# Parachute_V1.net
KiCad netlist of a schematic drawn in EAGLE
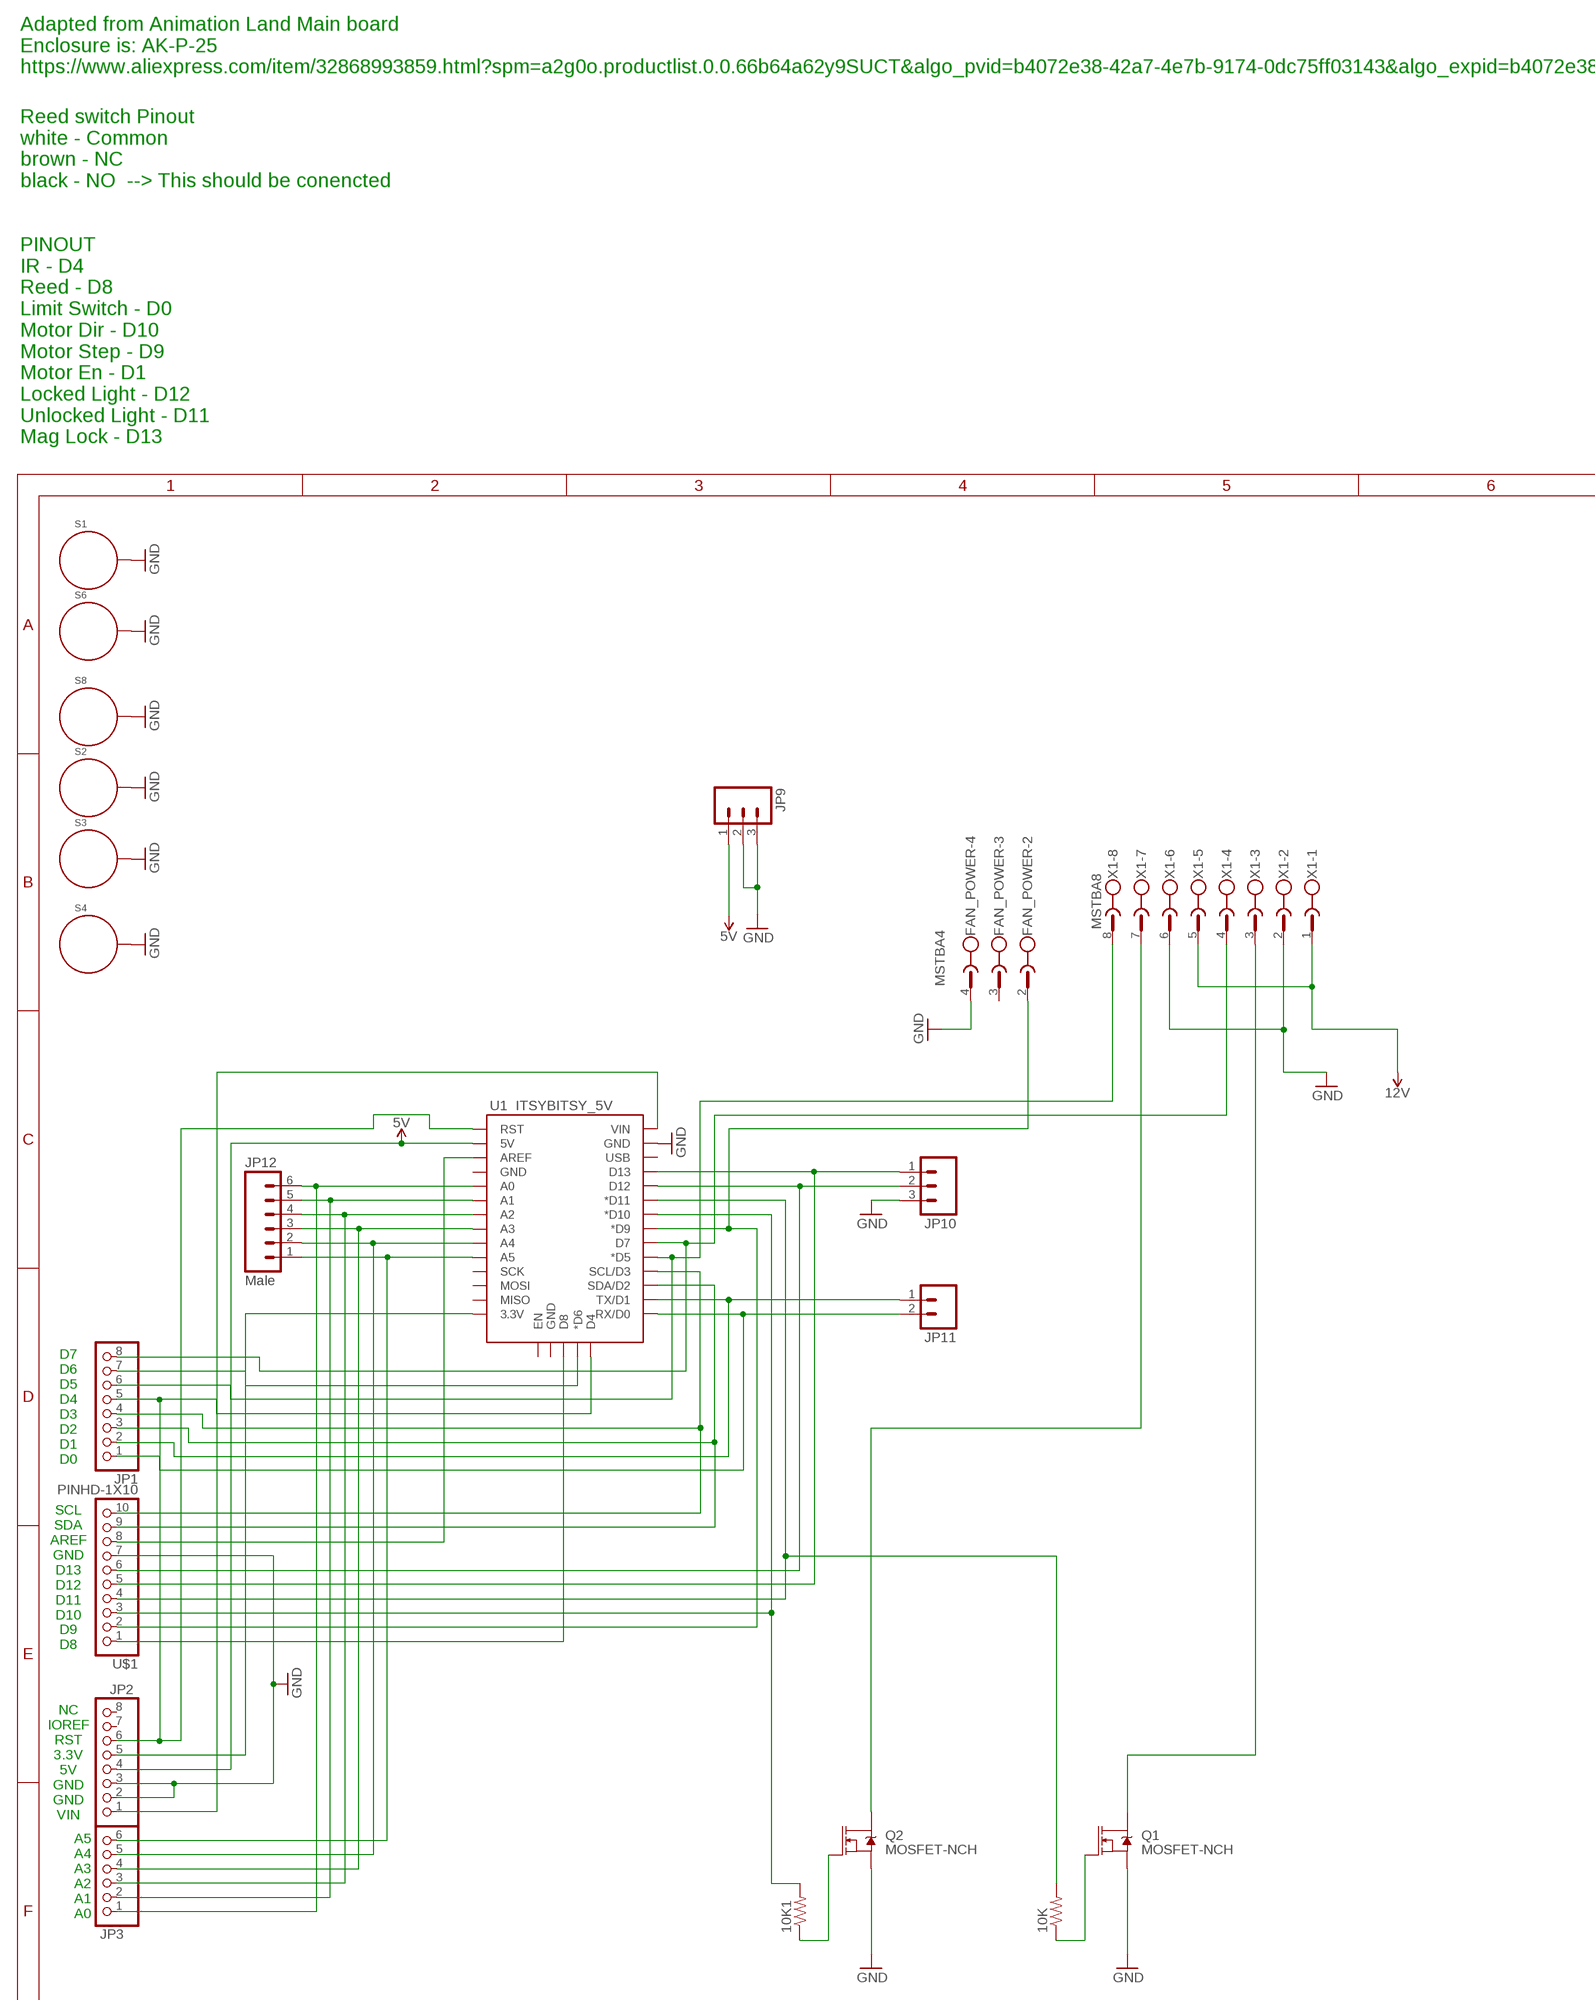
[diagram p0: schematic, sheet 1, part 1 of 2]
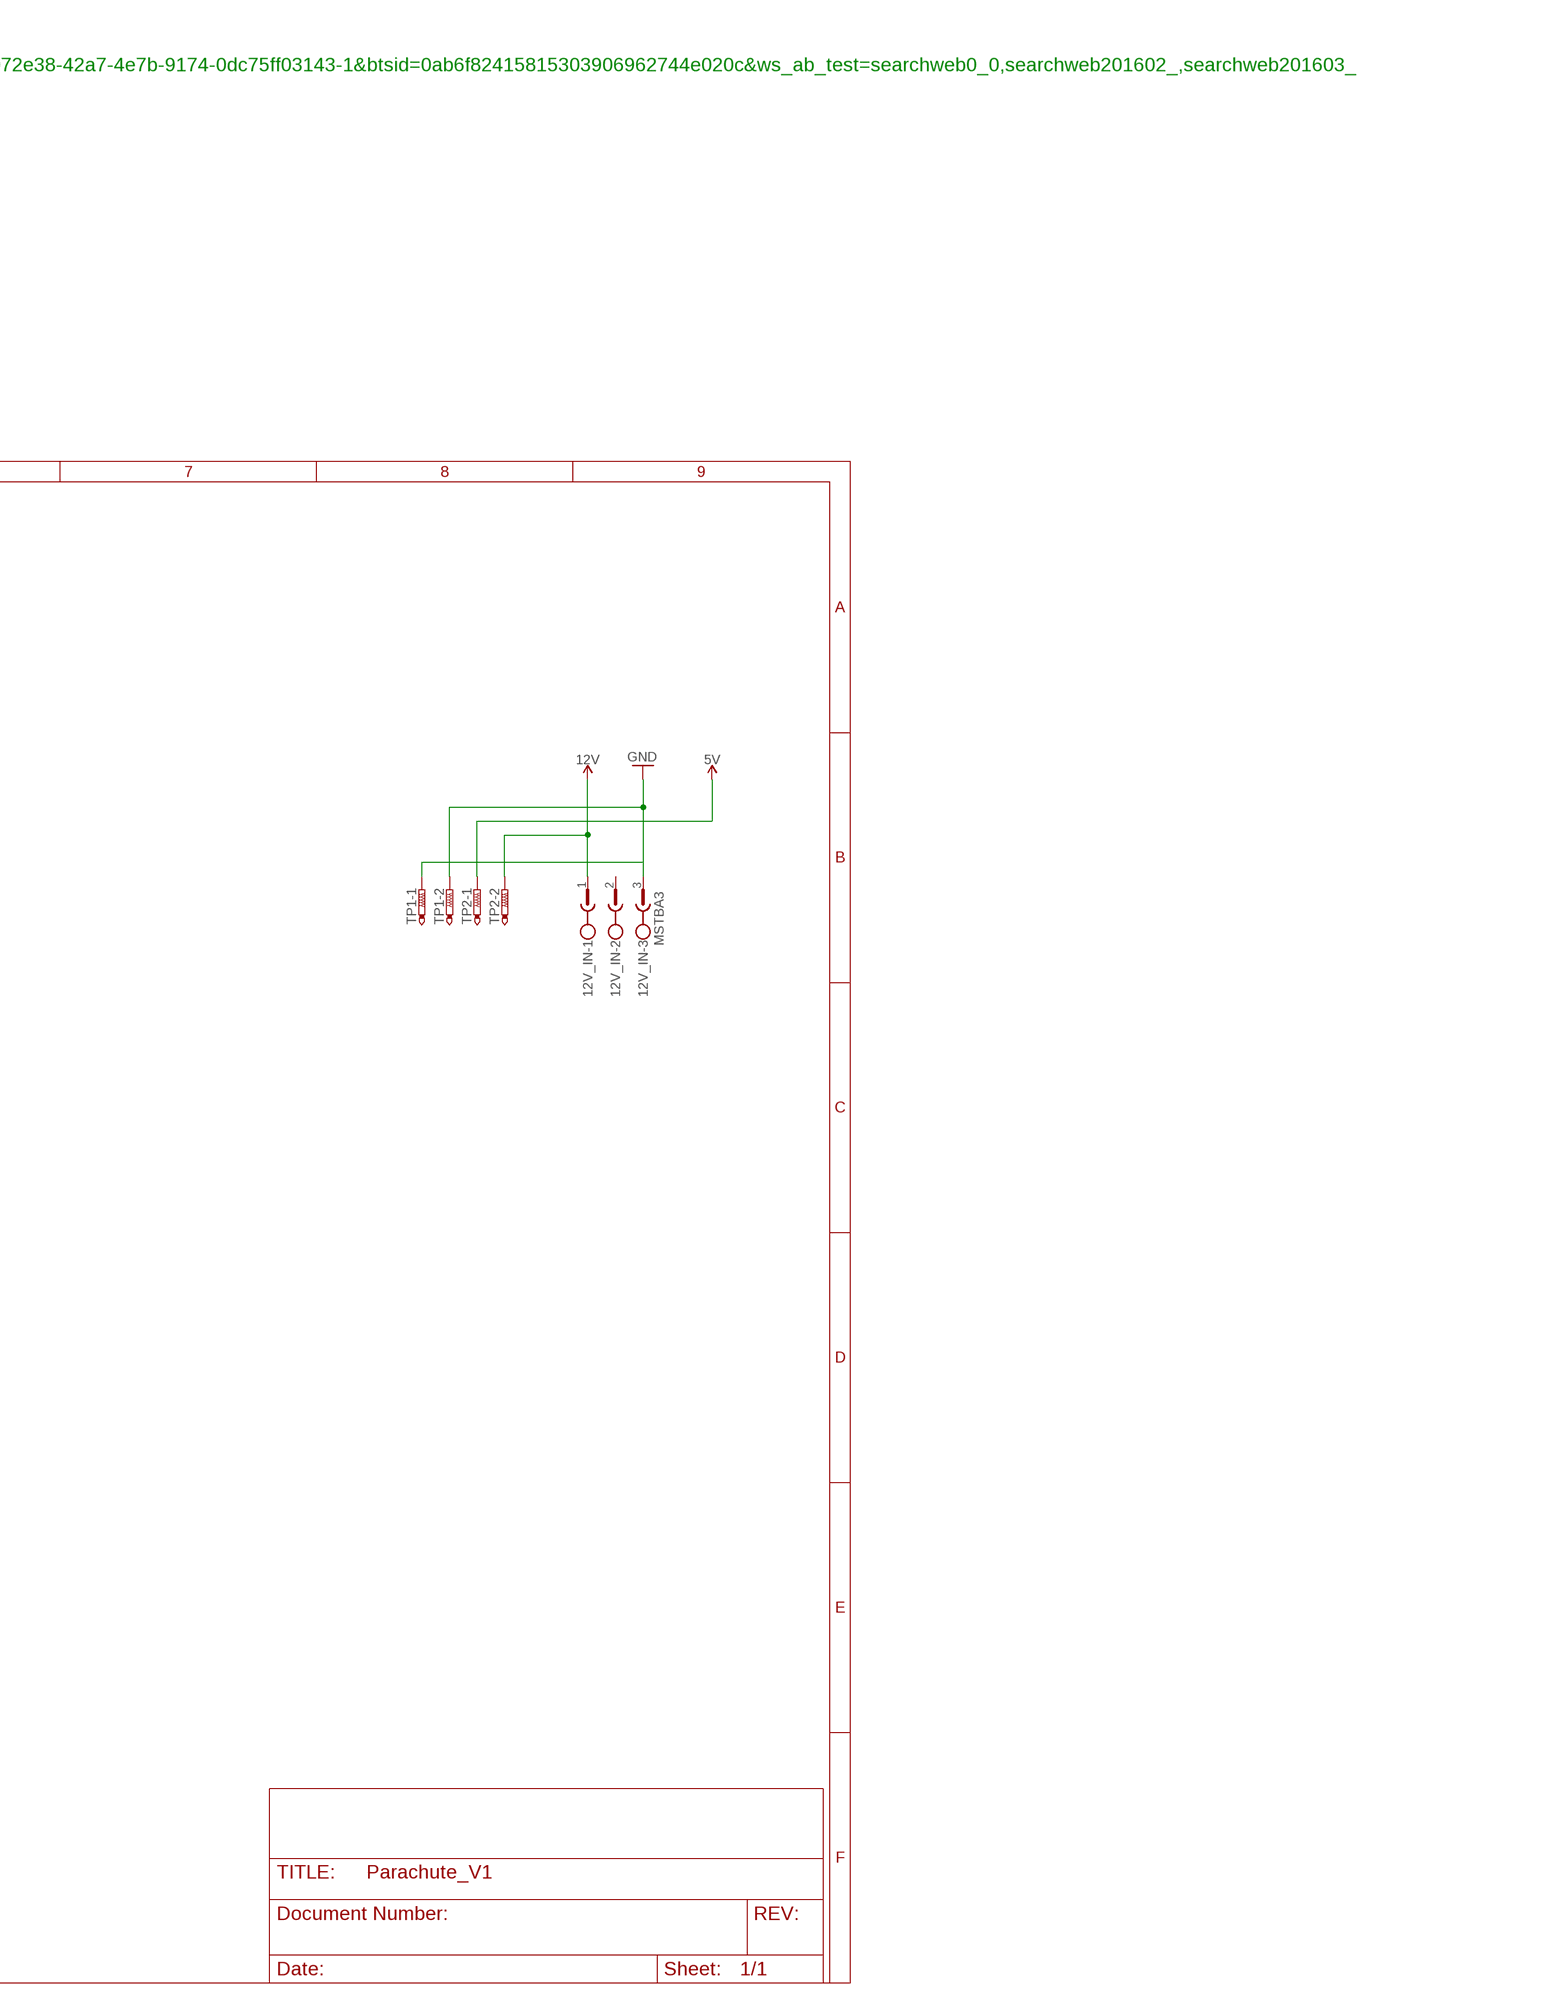
[diagram p1: schematic, sheet 1, part 2 of 2]

(export (version "E")
  (design (tool "Eeschema 10.0.6"))
  (components
    (comp (ref "10K")
      (value "R-US_M0805")
      (footprint "eagle-import:M0805")
      (libsource (lib "eagle-import") (part "R-US_M0805"))
    )
    (comp (ref "10K1")
      (value "R-US_M0805")
      (footprint "eagle-import:M0805")
      (libsource (lib "eagle-import") (part "R-US_M0805"))
    )
    (comp (ref "12V_IN")
      (value "MSTBA3")
      (footprint "eagle-import:MSTBA3")
      (fields (field (name "MF") "FARNELL") (field (name "MPN") "1757255"))
      (libsource (lib "eagle-import") (part "MSTBA3"))
    )
    (comp (ref "FAN_POWER")
      (value "MSTBA4")
      (footprint "eagle-import:MSTBA4")
      (fields (field (name "MF") "FARNELL") (field (name "MPN") "1757268"))
      (libsource (lib "eagle-import") (part "MSTBA4"))
    )
    (comp (ref "JP1")
      (value "PINHD-1X8CLEANBIG")
      (footprint "eagle-import:1X08-CLEANBIG")
      (libsource (lib "eagle-import") (part "PINHD-1X8CLEANBIG"))
    )
    (comp (ref "JP2")
      (value "PINHD-1X8CLEANBIG")
      (footprint "eagle-import:1X08-CLEANBIG")
      (libsource (lib "eagle-import") (part "PINHD-1X8CLEANBIG"))
    )
    (comp (ref "JP3")
      (value "PINHD-1X6B")
      (footprint "eagle-import:1X06-BIG")
      (libsource (lib "eagle-import") (part "PINHD-1X6B"))
    )
    (comp (ref "JP9")
      (value "M031X03_NO_SILK")
      (footprint "eagle-import:1X03_NO_SILK")
      (libsource (lib "eagle-import") (part "M031X03_NO_SILK"))
    )
    (comp (ref "JP10")
      (value "M031X03_NO_SILK")
      (footprint "eagle-import:1X03_NO_SILK")
      (libsource (lib "eagle-import") (part "M031X03_NO_SILK"))
    )
    (comp (ref "JP11")
      (value "M021X02_NO_SILK")
      (footprint "eagle-import:1X02_NO_SILK")
      (libsource (lib "eagle-import") (part "M021X02_NO_SILK"))
    )
    (comp (ref "JP12")
      (value "Male")
      (footprint "eagle-import:1X06")
      (libsource (lib "eagle-import") (part "M06SIP"))
    )
    (comp (ref "Q1")
      (value "MOSFET-NCH")
      (footprint "eagle-import:SO-8_POWER_PAK")
      (libsource (lib "eagle-import") (part "MOSFET-NCH"))
    )
    (comp (ref "Q2")
      (value "MOSFET-NCH")
      (footprint "eagle-import:SO-8_POWER_PAK")
      (libsource (lib "eagle-import") (part "MOSFET-NCH"))
    )
    (comp (ref "S1")
      (value "STANDOFF_ELECTRICAL5-32")
      (footprint "eagle-import:STANDOFF_ELECTRICAL_5_32")
      (libsource (lib "eagle-import") (part "STANDOFF_ELECTRICAL5-32"))
    )
    (comp (ref "S2")
      (value "STANDOFF_ELECTRICAL5-32")
      (footprint "eagle-import:STANDOFF_ELECTRICAL_5_32")
      (libsource (lib "eagle-import") (part "STANDOFF_ELECTRICAL5-32"))
    )
    (comp (ref "S3")
      (value "STANDOFF_ELECTRICAL5-32")
      (footprint "eagle-import:STANDOFF_ELECTRICAL_5_32")
      (libsource (lib "eagle-import") (part "STANDOFF_ELECTRICAL5-32"))
    )
    (comp (ref "S4")
      (value "STANDOFF_ELECTRICAL5-32")
      (footprint "eagle-import:STANDOFF_ELECTRICAL_5_32")
      (libsource (lib "eagle-import") (part "STANDOFF_ELECTRICAL5-32"))
    )
    (comp (ref "S6")
      (value "STANDOFF_ELECTRICAL5-32")
      (footprint "eagle-import:STANDOFF_ELECTRICAL_5_32")
      (libsource (lib "eagle-import") (part "STANDOFF_ELECTRICAL5-32"))
    )
    (comp (ref "S8")
      (value "STANDOFF_ELECTRICAL5-32")
      (footprint "eagle-import:STANDOFF_ELECTRICAL_5_32")
      (libsource (lib "eagle-import") (part "STANDOFF_ELECTRICAL5-32"))
    )
    (comp (ref "TP1")
      (value "PTR2")
      (footprint "eagle-import:P2-38-17")
      (libsource (lib "eagle-import") (part "PTR2"))
    )
    (comp (ref "TP2")
      (value "PTR2")
      (footprint "eagle-import:P2-38-17")
      (libsource (lib "eagle-import") (part "PTR2"))
    )
    (comp (ref "U$1")
      (value "PINHD-1X10")
      (footprint "eagle-import:1X10-BIG")
      (libsource (lib "eagle-import") (part "PINHD-1X10"))
    )
    (comp (ref "U1")
      (value "ITSYBITSY_5V")
      (footprint "eagle-import:ADAFRUIT_LENOARDO")
      (libsource (lib "eagle-import") (part "ITSYBITSY_5V"))
    )
    (comp (ref "X1")
      (value "MSTBA8")
      (footprint "eagle-import:MSTBA8")
      (fields (field (name "MF") "FARNELL") (field (name "MPN") "1757307"))
      (libsource (lib "eagle-import") (part "MSTBA8"))
    )
  )
  (nets
    (net (code "1") (name "5V") (class "Default")
      (node (ref "JP2") (pin "4") (pinfunction "4_4") (pintype "passive"))
      (node (ref "JP9") (pin "1") (pinfunction "1_1") (pintype "passive"))
      (node (ref "TP2") (pin "TP-1") (pinfunction "TP_TP-1") (pintype "input"))
      (node (ref "U1") (pin "5V") (pinfunction "5V_5V") (pintype "bidirectional"))
    )
    (net (code "2") (name "12V") (class "Default")
      (node (ref "12V_IN") (pin "1") (pinfunction "1_1") (pintype "passive"))
      (node (ref "TP2") (pin "TP-2") (pinfunction "TP_TP-2") (pintype "input"))
      (node (ref "X1") (pin "1") (pinfunction "1_1") (pintype "passive"))
      (node (ref "X1") (pin "5") (pinfunction "1_5") (pintype "passive"))
    )
    (net (code "3") (name "GND") (class "Default")
      (node (ref "12V_IN") (pin "3") (pinfunction "1_3") (pintype "passive"))
      (node (ref "FAN_POWER") (pin "4") (pinfunction "1_4") (pintype "passive"))
      (node (ref "JP10") (pin "3") (pinfunction "3_3") (pintype "passive"))
      (node (ref "JP2") (pin "2") (pinfunction "2_2") (pintype "passive"))
      (node (ref "JP2") (pin "3") (pinfunction "3_3") (pintype "passive"))
      (node (ref "JP9") (pin "2") (pinfunction "2_2") (pintype "passive"))
      (node (ref "JP9") (pin "3") (pinfunction "3_3") (pintype "passive"))
      (node (ref "Q1") (pin "S") (pinfunction "S_S") (pintype "bidirectional"))
      (node (ref "Q2") (pin "S") (pinfunction "S_S") (pintype "bidirectional"))
      (node (ref "S1") (pin "P1") (pinfunction "P$1_P1") (pintype "bidirectional"))
      (node (ref "S2") (pin "P1") (pinfunction "P$1_P1") (pintype "bidirectional"))
      (node (ref "S3") (pin "P1") (pinfunction "P$1_P1") (pintype "bidirectional"))
      (node (ref "S4") (pin "P1") (pinfunction "P$1_P1") (pintype "bidirectional"))
      (node (ref "S6") (pin "P1") (pinfunction "P$1_P1") (pintype "bidirectional"))
      (node (ref "S8") (pin "P1") (pinfunction "P$1_P1") (pintype "bidirectional"))
      (node (ref "TP1") (pin "TP-1") (pinfunction "TP_TP-1") (pintype "input"))
      (node (ref "TP1") (pin "TP-2") (pinfunction "TP_TP-2") (pintype "input"))
      (node (ref "U$1") (pin "7") (pinfunction "7_7") (pintype "passive"))
      (node (ref "U1") (pin "GND@2") (pinfunction "GND_GND@2") (pintype "bidirectional"))
      (node (ref "X1") (pin "2") (pinfunction "1_2") (pintype "passive"))
      (node (ref "X1") (pin "6") (pinfunction "1_6") (pintype "passive"))
    )
    (net (code "4") (name "Net-(10K-Pad1)") (class "Default")
      (node (ref "10K") (pin "1") (pinfunction "1_1") (pintype "passive"))
      (node (ref "Q1") (pin "G") (pinfunction "G_G") (pintype "bidirectional"))
    )
    (net (code "5") (name "Net-(10K1-Pad1)") (class "Default")
      (node (ref "10K1") (pin "1") (pinfunction "1_1") (pintype "passive"))
      (node (ref "Q2") (pin "G") (pinfunction "G_G") (pintype "bidirectional"))
    )
    (net (code "6") (name "Net-(FAN_POWERB-1)") (class "Default")
      (node (ref "FAN_POWER") (pin "2") (pinfunction "1_2") (pintype "passive"))
      (node (ref "U$1") (pin "2") (pinfunction "2_2") (pintype "passive"))
      (node (ref "U1") (pin "D9") (pinfunction "*D9_D9") (pintype "bidirectional"))
    )
    (net (code "7") (name "Net-(JP2-Pad1)") (class "Default")
      (node (ref "JP2") (pin "1") (pinfunction "1_1") (pintype "passive"))
      (node (ref "U1") (pin "VIN") (pinfunction "VIN_VIN") (pintype "bidirectional"))
    )
    (net (code "8") (name "Net-(JP10-Pad1)") (class "Default")
      (node (ref "JP10") (pin "1") (pinfunction "1_1") (pintype "passive"))
      (node (ref "U$1") (pin "5") (pinfunction "5_5") (pintype "passive"))
      (node (ref "U1") (pin "D13") (pinfunction "D13_D13") (pintype "bidirectional"))
    )
    (net (code "9") (name "Net-(JP10-Pad2)") (class "Default")
      (node (ref "JP10") (pin "2") (pinfunction "2_2") (pintype "passive"))
      (node (ref "U$1") (pin "6") (pinfunction "6_6") (pintype "passive"))
      (node (ref "U1") (pin "D12") (pinfunction "D12_D12") (pintype "bidirectional"))
    )
    (net (code "10") (name "Net-(JP12-Pad1)") (class "Default")
      (node (ref "JP12") (pin "1") (pinfunction "1_1") (pintype "passive"))
      (node (ref "JP3") (pin "6") (pinfunction "6_6") (pintype "passive"))
      (node (ref "U1") (pin "A5") (pinfunction "A5_A5") (pintype "bidirectional"))
    )
    (net (code "11") (name "Net-(JP12-Pad2)") (class "Default")
      (node (ref "JP12") (pin "2") (pinfunction "2_2") (pintype "passive"))
      (node (ref "JP3") (pin "5") (pinfunction "5_5") (pintype "passive"))
      (node (ref "U1") (pin "A4") (pinfunction "A4_A4") (pintype "bidirectional"))
    )
    (net (code "12") (name "Net-(JP12-Pad3)") (class "Default")
      (node (ref "JP12") (pin "3") (pinfunction "3_3") (pintype "passive"))
      (node (ref "JP3") (pin "4") (pinfunction "4_4") (pintype "passive"))
      (node (ref "U1") (pin "A3") (pinfunction "A3_A3") (pintype "bidirectional"))
    )
    (net (code "13") (name "Net-(JP12-Pad4)") (class "Default")
      (node (ref "JP12") (pin "4") (pinfunction "4_4") (pintype "passive"))
      (node (ref "JP3") (pin "3") (pinfunction "3_3") (pintype "passive"))
      (node (ref "U1") (pin "A2") (pinfunction "A2_A2") (pintype "bidirectional"))
    )
    (net (code "14") (name "Net-(JP12-Pad5)") (class "Default")
      (node (ref "JP12") (pin "5") (pinfunction "5_5") (pintype "passive"))
      (node (ref "JP3") (pin "2") (pinfunction "2_2") (pintype "passive"))
      (node (ref "U1") (pin "A1") (pinfunction "A1_A1") (pintype "bidirectional"))
    )
    (net (code "15") (name "Net-(JP12-Pad6)") (class "Default")
      (node (ref "JP12") (pin "6") (pinfunction "6_6") (pintype "passive"))
      (node (ref "JP3") (pin "1") (pinfunction "1_1") (pintype "passive"))
      (node (ref "U1") (pin "A0") (pinfunction "A0_A0") (pintype "bidirectional"))
    )
    (net (code "16") (name "Net-(Q1-D)") (class "Default")
      (node (ref "Q1") (pin "D1") (pinfunction "D_D1") (pintype "bidirectional"))
      (node (ref "X1") (pin "3") (pinfunction "1_3") (pintype "passive"))
    )
    (net (code "17") (name "Net-(Q2-D)") (class "Default")
      (node (ref "Q2") (pin "D1") (pinfunction "D_D1") (pintype "bidirectional"))
      (node (ref "X1") (pin "7") (pinfunction "1_7") (pintype "passive"))
    )
    (net (code "18") (name "Net-(U$1-Pad1)") (class "Default")
      (node (ref "U$1") (pin "1") (pinfunction "1_1") (pintype "passive"))
      (node (ref "U1") (pin "D8") (pinfunction "D8_D8") (pintype "bidirectional"))
    )
    (net (code "19") (name "Net-(U$1-Pad8)") (class "Default")
      (node (ref "U$1") (pin "8") (pinfunction "8_8") (pintype "passive"))
      (node (ref "U1") (pin "AREF") (pinfunction "AREF_AREF") (pintype "bidirectional"))
    )
    (net (code "20") (name "Net-(U1-*D5)") (class "Default")
      (node (ref "JP1") (pin "6") (pinfunction "6_6") (pintype "passive"))
      (node (ref "U1") (pin "D5") (pinfunction "*D5_D5") (pintype "bidirectional"))
      (node (ref "X1") (pin "8") (pinfunction "1_8") (pintype "passive"))
    )
    (net (code "21") (name "Net-(U1-*D6)") (class "Default")
      (node (ref "JP1") (pin "7") (pinfunction "7_7") (pintype "passive"))
      (node (ref "U1") (pin "D6") (pinfunction "*D6_D6") (pintype "bidirectional"))
    )
    (net (code "22") (name "Net-(U1-*D10)") (class "Default")
      (node (ref "10K1") (pin "2") (pinfunction "2_2") (pintype "passive"))
      (node (ref "U$1") (pin "3") (pinfunction "3_3") (pintype "passive"))
      (node (ref "U1") (pin "D10") (pinfunction "*D10_D10") (pintype "bidirectional"))
    )
    (net (code "23") (name "Net-(U1-*D11)") (class "Default")
      (node (ref "10K") (pin "2") (pinfunction "2_2") (pintype "passive"))
      (node (ref "U$1") (pin "4") (pinfunction "4_4") (pintype "passive"))
      (node (ref "U1") (pin "D11") (pinfunction "*D11_D11") (pintype "bidirectional"))
    )
    (net (code "24") (name "Net-(U1-3.3V)") (class "Default")
      (node (ref "JP2") (pin "5") (pinfunction "5_5") (pintype "passive"))
      (node (ref "U1") (pin "3V") (pinfunction "3.3V_3V") (pintype "bidirectional"))
    )
    (net (code "25") (name "Net-(U1-RST)") (class "Default")
      (node (ref "JP1") (pin "5") (pinfunction "5_5") (pintype "passive"))
      (node (ref "JP2") (pin "6") (pinfunction "6_6") (pintype "passive"))
      (node (ref "U1") (pin "D4") (pinfunction "D4_D4") (pintype "bidirectional"))
      (node (ref "U1") (pin "RES") (pinfunction "RST_RES") (pintype "bidirectional"))
    )
    (net (code "26") (name "Net-(U1-RX{slash}D0)") (class "Default")
      (node (ref "JP1") (pin "1") (pinfunction "1_1") (pintype "passive"))
      (node (ref "JP11") (pin "2") (pinfunction "2_2") (pintype "passive"))
      (node (ref "U1") (pin "RX") (pinfunction "RX/D0_RX") (pintype "bidirectional"))
    )
    (net (code "27") (name "Net-(U1-SCL{slash}D3)") (class "Default")
      (node (ref "JP1") (pin "4") (pinfunction "4_4") (pintype "passive"))
      (node (ref "U$1") (pin "10") (pinfunction "10_10") (pintype "passive"))
      (node (ref "U1") (pin "SCL") (pinfunction "SCL/D3_SCL") (pintype "bidirectional"))
    )
    (net (code "28") (name "Net-(U1-SDA{slash}D2)") (class "Default")
      (node (ref "JP1") (pin "3") (pinfunction "3_3") (pintype "passive"))
      (node (ref "U$1") (pin "9") (pinfunction "9_9") (pintype "passive"))
      (node (ref "U1") (pin "SDA") (pinfunction "SDA/D2_SDA") (pintype "bidirectional"))
    )
    (net (code "29") (name "Net-(U1-TX{slash}D1)") (class "Default")
      (node (ref "JP1") (pin "2") (pinfunction "2_2") (pintype "passive"))
      (node (ref "JP11") (pin "1") (pinfunction "1_1") (pintype "passive"))
      (node (ref "U1") (pin "TX") (pinfunction "TX/D1_TX") (pintype "bidirectional"))
    )
    (net (code "30") (name "Net-(X1D-1)") (class "Default")
      (node (ref "JP1") (pin "8") (pinfunction "8_8") (pintype "passive"))
      (node (ref "U1") (pin "D7") (pinfunction "D7_D7") (pintype "bidirectional"))
      (node (ref "X1") (pin "4") (pinfunction "1_4") (pintype "passive"))
    )
    (net (code "31") (name "unconnected-(12V_INB-1-Pad2)") (class "Default")
      (node (ref "12V_IN") (pin "2") (pinfunction "1_2") (pintype "passive"))
    )
    (net (code "32") (name "unconnected-(FAN_POWERC-1-Pad3)") (class "Default")
      (node (ref "FAN_POWER") (pin "3") (pinfunction "1_3") (pintype "passive"))
    )
    (net (code "33") (name "unconnected-(JP2-Pad7)") (class "Default")
      (node (ref "JP2") (pin "7") (pinfunction "7_7") (pintype "passive"))
    )
    (net (code "34") (name "unconnected-(JP2-Pad8)") (class "Default")
      (node (ref "JP2") (pin "8") (pinfunction "8_8") (pintype "passive"))
    )
    (net (code "35") (name "unconnected-(U1-GND-PadGND@0)") (class "Default")
      (node (ref "U1") (pin "GND@0") (pinfunction "GND_GND@0") (pintype "bidirectional"))
    )
    (net (code "36") (name "unconnected-(U1-GND-PadGND@1)") (class "Default")
      (node (ref "U1") (pin "GND@1") (pinfunction "GND_GND@1") (pintype "bidirectional"))
    )
    (net (code "37") (name "unconnected-(U1-PadEN)") (class "Default")
      (node (ref "U1") (pin "EN") (pinfunction "EN_EN") (pintype "bidirectional"))
    )
    (net (code "38") (name "unconnected-(U1-PadMISO)") (class "Default")
      (node (ref "U1") (pin "MISO") (pinfunction "MISO_MISO") (pintype "bidirectional"))
    )
    (net (code "39") (name "unconnected-(U1-PadMOSI)") (class "Default")
      (node (ref "U1") (pin "MOSI") (pinfunction "MOSI_MOSI") (pintype "bidirectional"))
    )
    (net (code "40") (name "unconnected-(U1-PadSCK)") (class "Default")
      (node (ref "U1") (pin "SCK") (pinfunction "SCK_SCK") (pintype "bidirectional"))
    )
    (net (code "41") (name "unconnected-(U1-PadUSB)") (class "Default")
      (node (ref "U1") (pin "USB") (pinfunction "USB_USB") (pintype "bidirectional"))
    )
  )
)
